# Radio.net
KiCad netlist of a schematic drawn in Altium Designer
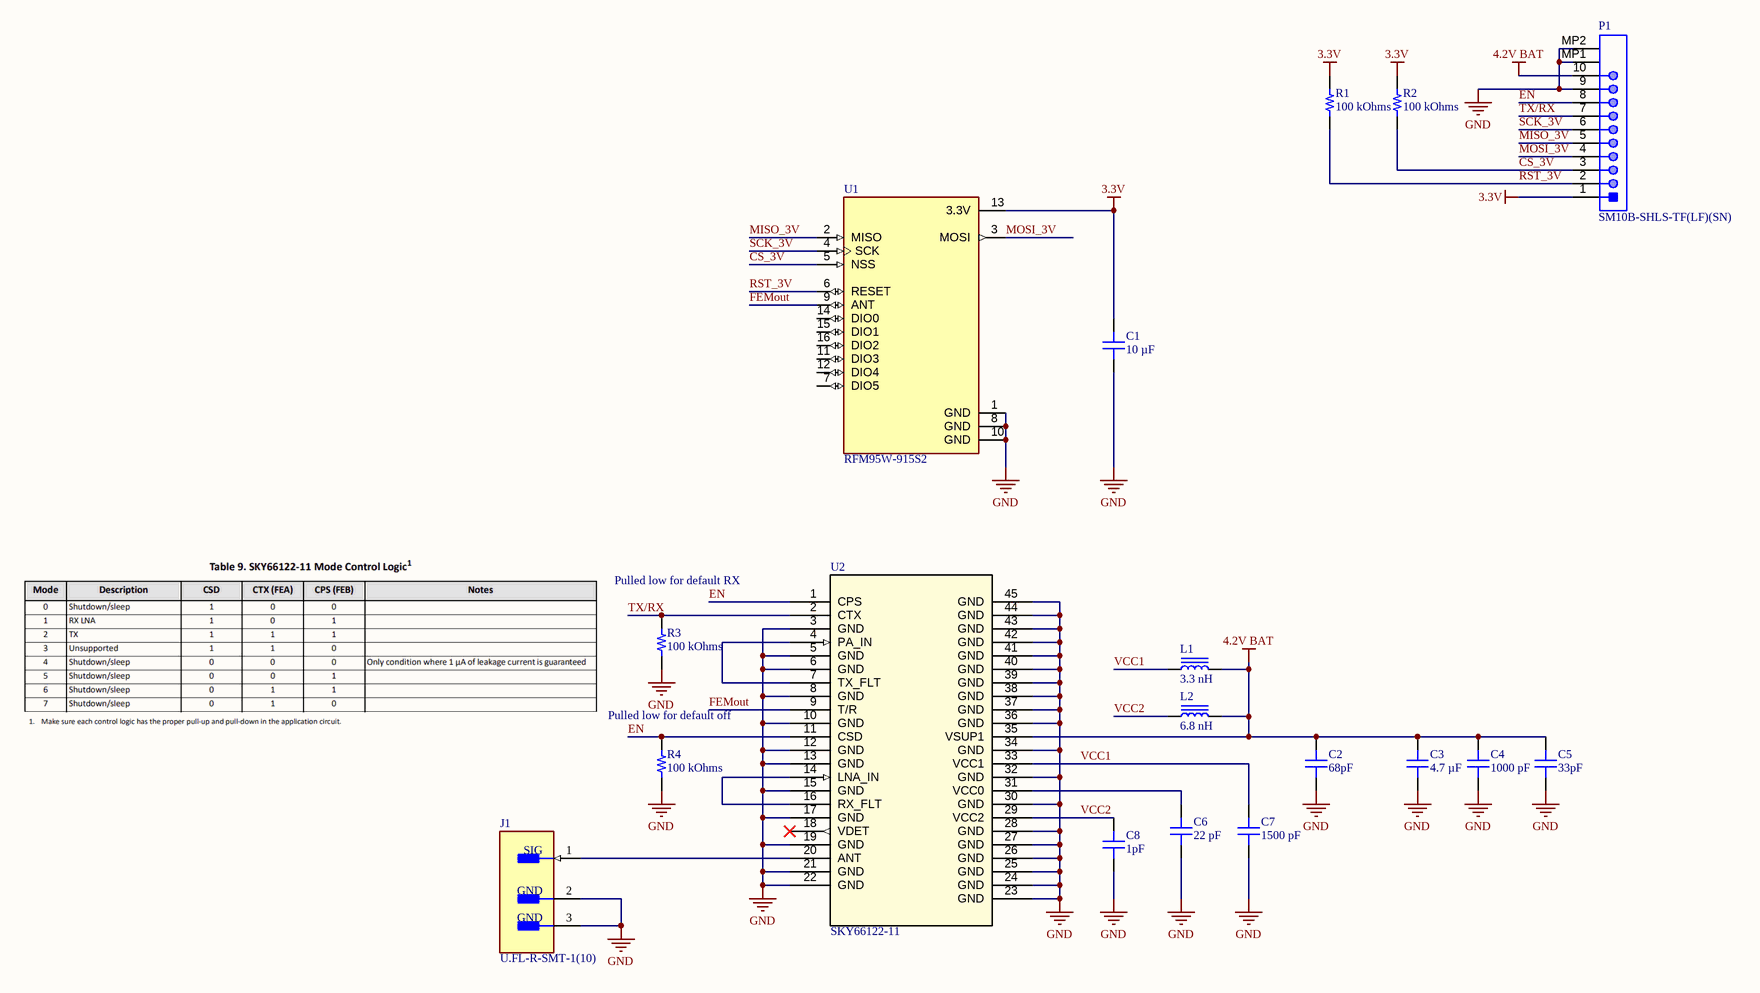
[diagram p0: Radio.SchDoc]

(export (version "E")
  (design (tool "Eeschema 10.0.6"))
  (components
    (comp (ref "C1")
      (value "10 µF")
      (footprint "CAP 0805_2012")
      (description "CAP CER 10UF 10V X7R 0805")
      (fields
        (field (name "PART NUMBER") "MD0805BB106M100NHT-EM")
        (field (name "CAPACITANCE") "10 µF")
        (field (name "MANUFACTURER") "Knowles Novacap")
      )
      (libsource (lib "Celestial Altium Library - altium_library") (part "Capacitor"))
    )
    (comp (ref "C2")
      (value "68pF")
      (footprint "CAP 0805_2012")
      (description "CAP CER 68PF 50V C0G/NP0 0805")
      (fields
        (field (name "PART NUMBER") "08055A680JAT2A")
        (field (name "CAPACITANCE") "68pF")
        (field (name "MANUFACTURER") "AVX Corporation")
      )
      (libsource (lib "Celestial Altium Library - altium_library") (part "Capacitor"))
    )
    (comp (ref "C3")
      (value "4.7 µF")
      (footprint "CAP 0805_2012")
      (description "CAP CER 4.7UF 25V X7R 0805")
      (fields
        (field (name "PART NUMBER") "CL21B475KAFNNNE")
        (field (name "CAPACITANCE") "4.7 µF")
        (field (name "MANUFACTURER") "Samsung Electro-Mechanics")
      )
      (libsource (lib "Celestial Altium Library - altium_library") (part "Capacitor"))
    )
    (comp (ref "C4")
      (value "1000 pF")
      (footprint "CAP 0805_2012")
      (description "CAP CER 0805 1NF 50V ULTRA STABL")
      (fields
        (field (name "PART NUMBER") "C0805X102J5HACAUTO")
        (field (name "CAPACITANCE") "1000 pF")
        (field (name "MANUFACTURER") "KEMET")
      )
      (libsource (lib "Celestial Altium Library - altium_library") (part "Capacitor"))
    )
    (comp (ref "C5")
      (value "33pF")
      (footprint "CAP 0805_2012")
      (description "CAP CER 33PF 50V X7R 0805")
      (fields
        (field (name "PART NUMBER") "08055C330KAT2A")
        (field (name "CAPACITANCE") "33pF")
        (field (name "MANUFACTURER") "AVX Corporation")
      )
      (libsource (lib "Celestial Altium Library - altium_library") (part "Capacitor"))
    )
    (comp (ref "C6")
      (value "22 pF")
      (footprint "CAP 0805_2012")
      (description "CAP CER 22PF 50V C0G/NP0 0805")
      (fields
        (field (name "PART NUMBER") "C0805C220J5GACAUTO")
        (field (name "CAPACITANCE") "22 pF")
        (field (name "MANUFACTURER") "KEMET")
      )
      (libsource (lib "Celestial Altium Library - altium_library") (part "Capacitor"))
    )
    (comp (ref "C7")
      (value "1500 pF")
      (footprint "CAP 0805_2012")
      (description "CAP CER 1500PF 250V X7R 0805")
      (fields
        (field (name "PART NUMBER") "C0805C152KARAC7800")
        (field (name "CAPACITANCE") "1500 pF")
        (field (name "MANUFACTURER") "KEMET")
      )
      (libsource (lib "Celestial Altium Library - altium_library") (part "Capacitor"))
    )
    (comp (ref "C8")
      (value "1pF")
      (footprint "CAP 0805_2012")
      (description "CAP CER 1PF 50V C0G/NP0 0805")
      (fields
        (field (name "PART NUMBER") "08055A1R0CAT2A")
        (field (name "CAPACITANCE") "1pF")
        (field (name "MANUFACTURER") "AVX Corporation")
      )
      (libsource (lib "Celestial Altium Library - altium_library") (part "Capacitor"))
    )
    (comp (ref "J1")
      (value "U.FL-R-SMT-1(10)")
      (footprint "FP-U_FL-R-SMT-1_10-MFG")
      (description "CONN U.FL RCPT STR 50 OHM SMD")
      (libsource (lib "Altium Content Vault") (part "7158abf7d987fa84906f6fb0d115710"))
    )
    (comp (ref "L1")
      (value "3.3 nH")
      (footprint "IND 0402_1005")
      (description "FIXED IND 3.3NH 1.7A 45 MOHM SMD")
      (fields (field (name "PART NUMBER") "AISC-0402HP-3N3J-T") (field (name "MANUFACTURER") "Abracon LLC"))
      (libsource (lib "Celestial Altium Library - altium_library") (part "Inductor"))
    )
    (comp (ref "L2")
      (value "6.8 nH")
      (footprint "IND 0402_1005")
      (description "FIXED IND 6.8NH 1.4A 65 MOHM SMD")
      (fields (field (name "PART NUMBER") "AISC-0402HP-6N8J-T") (field (name "MANUFACTURER") "Abracon LLC"))
      (libsource (lib "Celestial Altium Library - altium_library") (part "Inductor"))
    )
    (comp (ref "P1")
      (value "SM10B-SHLS-TF(LF)(SN)")
      (footprint "JST-SM10B-SHLS-TF_V")
      (description "Male Header, Pitch 1 mm, 1 x 10 Position, Height 1.8 mm, -25 to 85 degC")
      (fields (field (name "MANUFACTURER") "JST"))
      (libsource (lib "Altium Content Vault") (part "CN-1P-2M-R10"))
    )
    (comp (ref "R1")
      (value "100 kOhms")
      (footprint "RES 0805_2012")
      (description "RES SMD 100K OHM 0.1% 1/10W 0805")
      (fields
        (field (name "PART NUMBER") "CPF0805B100KE")
        (field (name "MANUFACTURER") "TE Connectivity Passive Product")
      )
      (libsource (lib "Celestial Altium Library - altium_library") (part "Resistor"))
    )
    (comp (ref "R2")
      (value "100 kOhms")
      (footprint "RES 0805_2012")
      (description "RES SMD 100K OHM 0.1% 1/10W 0805")
      (fields
        (field (name "PART NUMBER") "CPF0805B100KE")
        (field (name "MANUFACTURER") "TE Connectivity Passive Product")
      )
      (libsource (lib "Celestial Altium Library - altium_library") (part "Resistor"))
    )
    (comp (ref "R3")
      (value "100 kOhms")
      (footprint "RES 0805_2012")
      (description "RES SMD 100K OHM 0.1% 1/10W 0805")
      (fields
        (field (name "PART NUMBER") "CPF0805B100KE")
        (field (name "MANUFACTURER") "TE Connectivity Passive Product")
      )
      (libsource (lib "Celestial Altium Library - altium_library") (part "Resistor"))
    )
    (comp (ref "R4")
      (value "100 kOhms")
      (footprint "RES 0805_2012")
      (description "RES SMD 100K OHM 0.1% 1/10W 0805")
      (fields
        (field (name "PART NUMBER") "CPF0805B100KE")
        (field (name "MANUFACTURER") "TE Connectivity Passive Product")
      )
      (libsource (lib "Celestial Altium Library - altium_library") (part "Resistor"))
    )
    (comp (ref "U1")
      (value "RFM95W-915S2")
      (footprint "XCVR_RFM95W-915S2")
      (description "RFM95(W) - Low Power Long Range Transceiver Module V1.0")
      (libsource (lib "RFM95W-915S2") (part "RFM95W-915S2"))
    )
    (comp (ref "U2")
      (value "SKY66122-11")
      (footprint "SKY66122-11_SKY")
      (description "No Description Available")
      (libsource (lib "Andrew McDonald") (part "SKY66122-11"))
    )
  )
  (nets
    (net (code "1") (name "/CS_3V") (class "Default")
      (node (ref "P1") (pin "3") (pinfunction "3_3") (pintype "passive"))
      (node (ref "R2") (pin "1") (pinfunction "1_1") (pintype "passive"))
      (node (ref "U1") (pin "5") (pinfunction "NSS_5") (pintype "input"))
    )
    (net (code "2") (name "/EN") (class "Default")
      (node (ref "P1") (pin "8") (pinfunction "8_8") (pintype "passive"))
      (node (ref "R4") (pin "2") (pinfunction "2_2") (pintype "passive"))
      (node (ref "U2") (pin "1") (pinfunction "CPS_1") (pintype "passive"))
      (node (ref "U2") (pin "11") (pinfunction "CSD_11") (pintype "power_in"))
    )
    (net (code "3") (name "/FEMout") (class "Default")
      (node (ref "U1") (pin "9") (pinfunction "ANT_9") (pintype "bidirectional"))
      (node (ref "U2") (pin "9") (pinfunction "T/R_9") (pintype "passive"))
    )
    (net (code "4") (name "/MISO_3V") (class "Default")
      (node (ref "P1") (pin "5") (pinfunction "5_5") (pintype "passive"))
      (node (ref "U1") (pin "2") (pinfunction "MISO_2") (pintype "input"))
    )
    (net (code "5") (name "/MOSI_3V") (class "Default")
      (node (ref "P1") (pin "4") (pinfunction "4_4") (pintype "passive"))
      (node (ref "U1") (pin "3") (pinfunction "MOSI_3") (pintype "output"))
    )
    (net (code "6") (name "/RST_3V") (class "Default")
      (node (ref "P1") (pin "2") (pinfunction "2_2") (pintype "passive"))
      (node (ref "R1") (pin "1") (pinfunction "1_1") (pintype "passive"))
      (node (ref "U1") (pin "6") (pinfunction "RESET_6") (pintype "bidirectional"))
    )
    (net (code "7") (name "/SCK_3V") (class "Default")
      (node (ref "P1") (pin "6") (pinfunction "6_6") (pintype "passive"))
      (node (ref "U1") (pin "4") (pinfunction "SCK_4") (pintype "input"))
    )
    (net (code "8") (name "/TX{slash}RX") (class "Default")
      (node (ref "P1") (pin "7") (pinfunction "7_7") (pintype "passive"))
      (node (ref "R3") (pin "2") (pinfunction "2_2") (pintype "passive"))
      (node (ref "U2") (pin "2") (pinfunction "CTX_2") (pintype "passive"))
    )
    (net (code "9") (name "/VCC1") (class "Default")
      (node (ref "C7") (pin "2") (pinfunction "2_2") (pintype "passive"))
      (node (ref "L1") (pin "1") (pinfunction "1_1") (pintype "passive"))
      (node (ref "U2") (pin "33") (pinfunction "VCC1_33") (pintype "power_in"))
    )
    (net (code "10") (name "/VCC2") (class "Default")
      (node (ref "C8") (pin "2") (pinfunction "2_2") (pintype "passive"))
      (node (ref "L2") (pin "1") (pinfunction "1_1") (pintype "passive"))
      (node (ref "U2") (pin "29") (pinfunction "VCC2_29") (pintype "power_in"))
    )
    (net (code "11") (name "3.3V") (class "Default")
      (node (ref "C1") (pin "2") (pinfunction "2_2") (pintype "passive"))
      (node (ref "P1") (pin "1") (pinfunction "1_1") (pintype "passive"))
      (node (ref "R1") (pin "2") (pinfunction "2_2") (pintype "passive"))
      (node (ref "R2") (pin "2") (pinfunction "2_2") (pintype "passive"))
      (node (ref "U1") (pin "13") (pinfunction "3.3V_13") (pintype "power_in"))
    )
    (net (code "12") (name "4.2V BAT") (class "Default")
      (node (ref "C2") (pin "2") (pinfunction "2_2") (pintype "passive"))
      (node (ref "C3") (pin "2") (pinfunction "2_2") (pintype "passive"))
      (node (ref "C4") (pin "2") (pinfunction "2_2") (pintype "passive"))
      (node (ref "C5") (pin "2") (pinfunction "2_2") (pintype "passive"))
      (node (ref "L1") (pin "2") (pinfunction "2_2") (pintype "passive"))
      (node (ref "L2") (pin "2") (pinfunction "2_2") (pintype "passive"))
      (node (ref "P1") (pin "10") (pinfunction "10_10") (pintype "passive"))
      (node (ref "U2") (pin "35") (pinfunction "VSUP1_35") (pintype "power_in"))
    )
    (net (code "13") (name "GND") (class "Default")
      (node (ref "C1") (pin "1") (pinfunction "1_1") (pintype "passive"))
      (node (ref "C2") (pin "1") (pinfunction "1_1") (pintype "passive"))
      (node (ref "C3") (pin "1") (pinfunction "1_1") (pintype "passive"))
      (node (ref "C4") (pin "1") (pinfunction "1_1") (pintype "passive"))
      (node (ref "C5") (pin "1") (pinfunction "1_1") (pintype "passive"))
      (node (ref "C6") (pin "1") (pinfunction "1_1") (pintype "passive"))
      (node (ref "C7") (pin "1") (pinfunction "1_1") (pintype "passive"))
      (node (ref "C8") (pin "1") (pinfunction "1_1") (pintype "passive"))
      (node (ref "J1") (pin "2") (pinfunction "GND_2") (pintype "power_in"))
      (node (ref "J1") (pin "3") (pinfunction "GND_3") (pintype "power_in"))
      (node (ref "P1") (pin "9") (pinfunction "9_9") (pintype "passive"))
      (node (ref "P1") (pin "MP1") (pinfunction "MP1_MP1") (pintype "passive"))
      (node (ref "P1") (pin "MP2") (pinfunction "MP2_MP2") (pintype "passive"))
      (node (ref "R3") (pin "1") (pinfunction "1_1") (pintype "passive"))
      (node (ref "R4") (pin "1") (pinfunction "1_1") (pintype "passive"))
      (node (ref "U1") (pin "1") (pinfunction "GND_1") (pintype "power_in"))
      (node (ref "U1") (pin "10") (pinfunction "GND_10") (pintype "power_in"))
      (node (ref "U1") (pin "8") (pinfunction "GND_8") (pintype "power_in"))
      (node (ref "U2") (pin "10") (pinfunction "GND_10") (pintype "power_in"))
      (node (ref "U2") (pin "12") (pinfunction "GND_12") (pintype "power_in"))
      (node (ref "U2") (pin "13") (pinfunction "GND_13") (pintype "power_in"))
      (node (ref "U2") (pin "15") (pinfunction "GND_15") (pintype "power_in"))
      (node (ref "U2") (pin "17") (pinfunction "GND_17") (pintype "power_in"))
      (node (ref "U2") (pin "19") (pinfunction "GND_19") (pintype "power_in"))
      (node (ref "U2") (pin "21") (pinfunction "GND_21") (pintype "power_in"))
      (node (ref "U2") (pin "22") (pinfunction "GND_22") (pintype "power_in"))
      (node (ref "U2") (pin "23") (pinfunction "GND_23") (pintype "power_in"))
      (node (ref "U2") (pin "24") (pinfunction "GND_24") (pintype "power_in"))
      (node (ref "U2") (pin "25") (pinfunction "GND_25") (pintype "power_in"))
      (node (ref "U2") (pin "26") (pinfunction "GND_26") (pintype "power_in"))
      (node (ref "U2") (pin "27") (pinfunction "GND_27") (pintype "power_in"))
      (node (ref "U2") (pin "28") (pinfunction "GND_28") (pintype "power_in"))
      (node (ref "U2") (pin "3") (pinfunction "GND_3") (pintype "power_in"))
      (node (ref "U2") (pin "30") (pinfunction "GND_30") (pintype "power_in"))
      (node (ref "U2") (pin "32") (pinfunction "GND_32") (pintype "power_in"))
      (node (ref "U2") (pin "34") (pinfunction "GND_34") (pintype "power_in"))
      (node (ref "U2") (pin "36") (pinfunction "GND_36") (pintype "power_in"))
      (node (ref "U2") (pin "37") (pinfunction "GND_37") (pintype "power_in"))
      (node (ref "U2") (pin "38") (pinfunction "GND_38") (pintype "power_in"))
      (node (ref "U2") (pin "39") (pinfunction "GND_39") (pintype "power_in"))
      (node (ref "U2") (pin "40") (pinfunction "GND_40") (pintype "power_in"))
      (node (ref "U2") (pin "41") (pinfunction "GND_41") (pintype "power_in"))
      (node (ref "U2") (pin "42") (pinfunction "GND_42") (pintype "power_in"))
      (node (ref "U2") (pin "43") (pinfunction "GND_43") (pintype "power_in"))
      (node (ref "U2") (pin "44") (pinfunction "GND_44") (pintype "power_in"))
      (node (ref "U2") (pin "45") (pinfunction "GND_45") (pintype "power_in"))
      (node (ref "U2") (pin "5") (pinfunction "GND_5") (pintype "power_in"))
      (node (ref "U2") (pin "6") (pinfunction "GND_6") (pintype "power_in"))
      (node (ref "U2") (pin "8") (pinfunction "GND_8") (pintype "power_in"))
    )
    (net (code "14") (name "Net-(J1-SIG)") (class "Default")
      (node (ref "J1") (pin "1") (pinfunction "SIG_1") (pintype "input"))
      (node (ref "U2") (pin "20") (pinfunction "ANT_20") (pintype "passive"))
    )
    (net (code "15") (name "Net-(U2-LNA_IN)") (class "Default")
      (node (ref "U2") (pin "14") (pinfunction "LNA_IN_14") (pintype "input"))
      (node (ref "U2") (pin "16") (pinfunction "RX_FLT_16") (pintype "passive"))
    )
    (net (code "16") (name "Net-(U2-PA_IN)") (class "Default")
      (node (ref "U2") (pin "4") (pinfunction "PA_IN_4") (pintype "input"))
      (node (ref "U2") (pin "7") (pinfunction "TX_FLT_7") (pintype "passive"))
    )
    (net (code "17") (name "Net-(U2-VCC0)") (class "Default")
      (node (ref "C6") (pin "2") (pinfunction "2_2") (pintype "passive"))
      (node (ref "U2") (pin "31") (pinfunction "VCC0_31") (pintype "power_in"))
    )
    (net (code "18") (name "unconnected-(U1-DIO0-Pad14)") (class "Default")
      (node (ref "U1") (pin "14") (pinfunction "DIO0_14") (pintype "bidirectional"))
    )
    (net (code "19") (name "unconnected-(U1-DIO1-Pad15)") (class "Default")
      (node (ref "U1") (pin "15") (pinfunction "DIO1_15") (pintype "bidirectional"))
    )
    (net (code "20") (name "unconnected-(U1-DIO2-Pad16)") (class "Default")
      (node (ref "U1") (pin "16") (pinfunction "DIO2_16") (pintype "bidirectional"))
    )
    (net (code "21") (name "unconnected-(U1-DIO3-Pad11)") (class "Default")
      (node (ref "U1") (pin "11") (pinfunction "DIO3_11") (pintype "bidirectional"))
    )
    (net (code "22") (name "unconnected-(U1-DIO4-Pad12)") (class "Default")
      (node (ref "U1") (pin "12") (pinfunction "DIO4_12") (pintype "bidirectional"))
    )
    (net (code "23") (name "unconnected-(U1-DIO5-Pad7)") (class "Default")
      (node (ref "U1") (pin "7") (pinfunction "DIO5_7") (pintype "bidirectional"))
    )
    (net (code "24") (name "unconnected-(U2-VDET-Pad18)") (class "Default")
      (node (ref "U2") (pin "18") (pinfunction "VDET_18") (pintype "output+no_connect"))
    )
  )
)
